# ac_proj.net
KiCad netlist of a schematic drawn in EAGLE
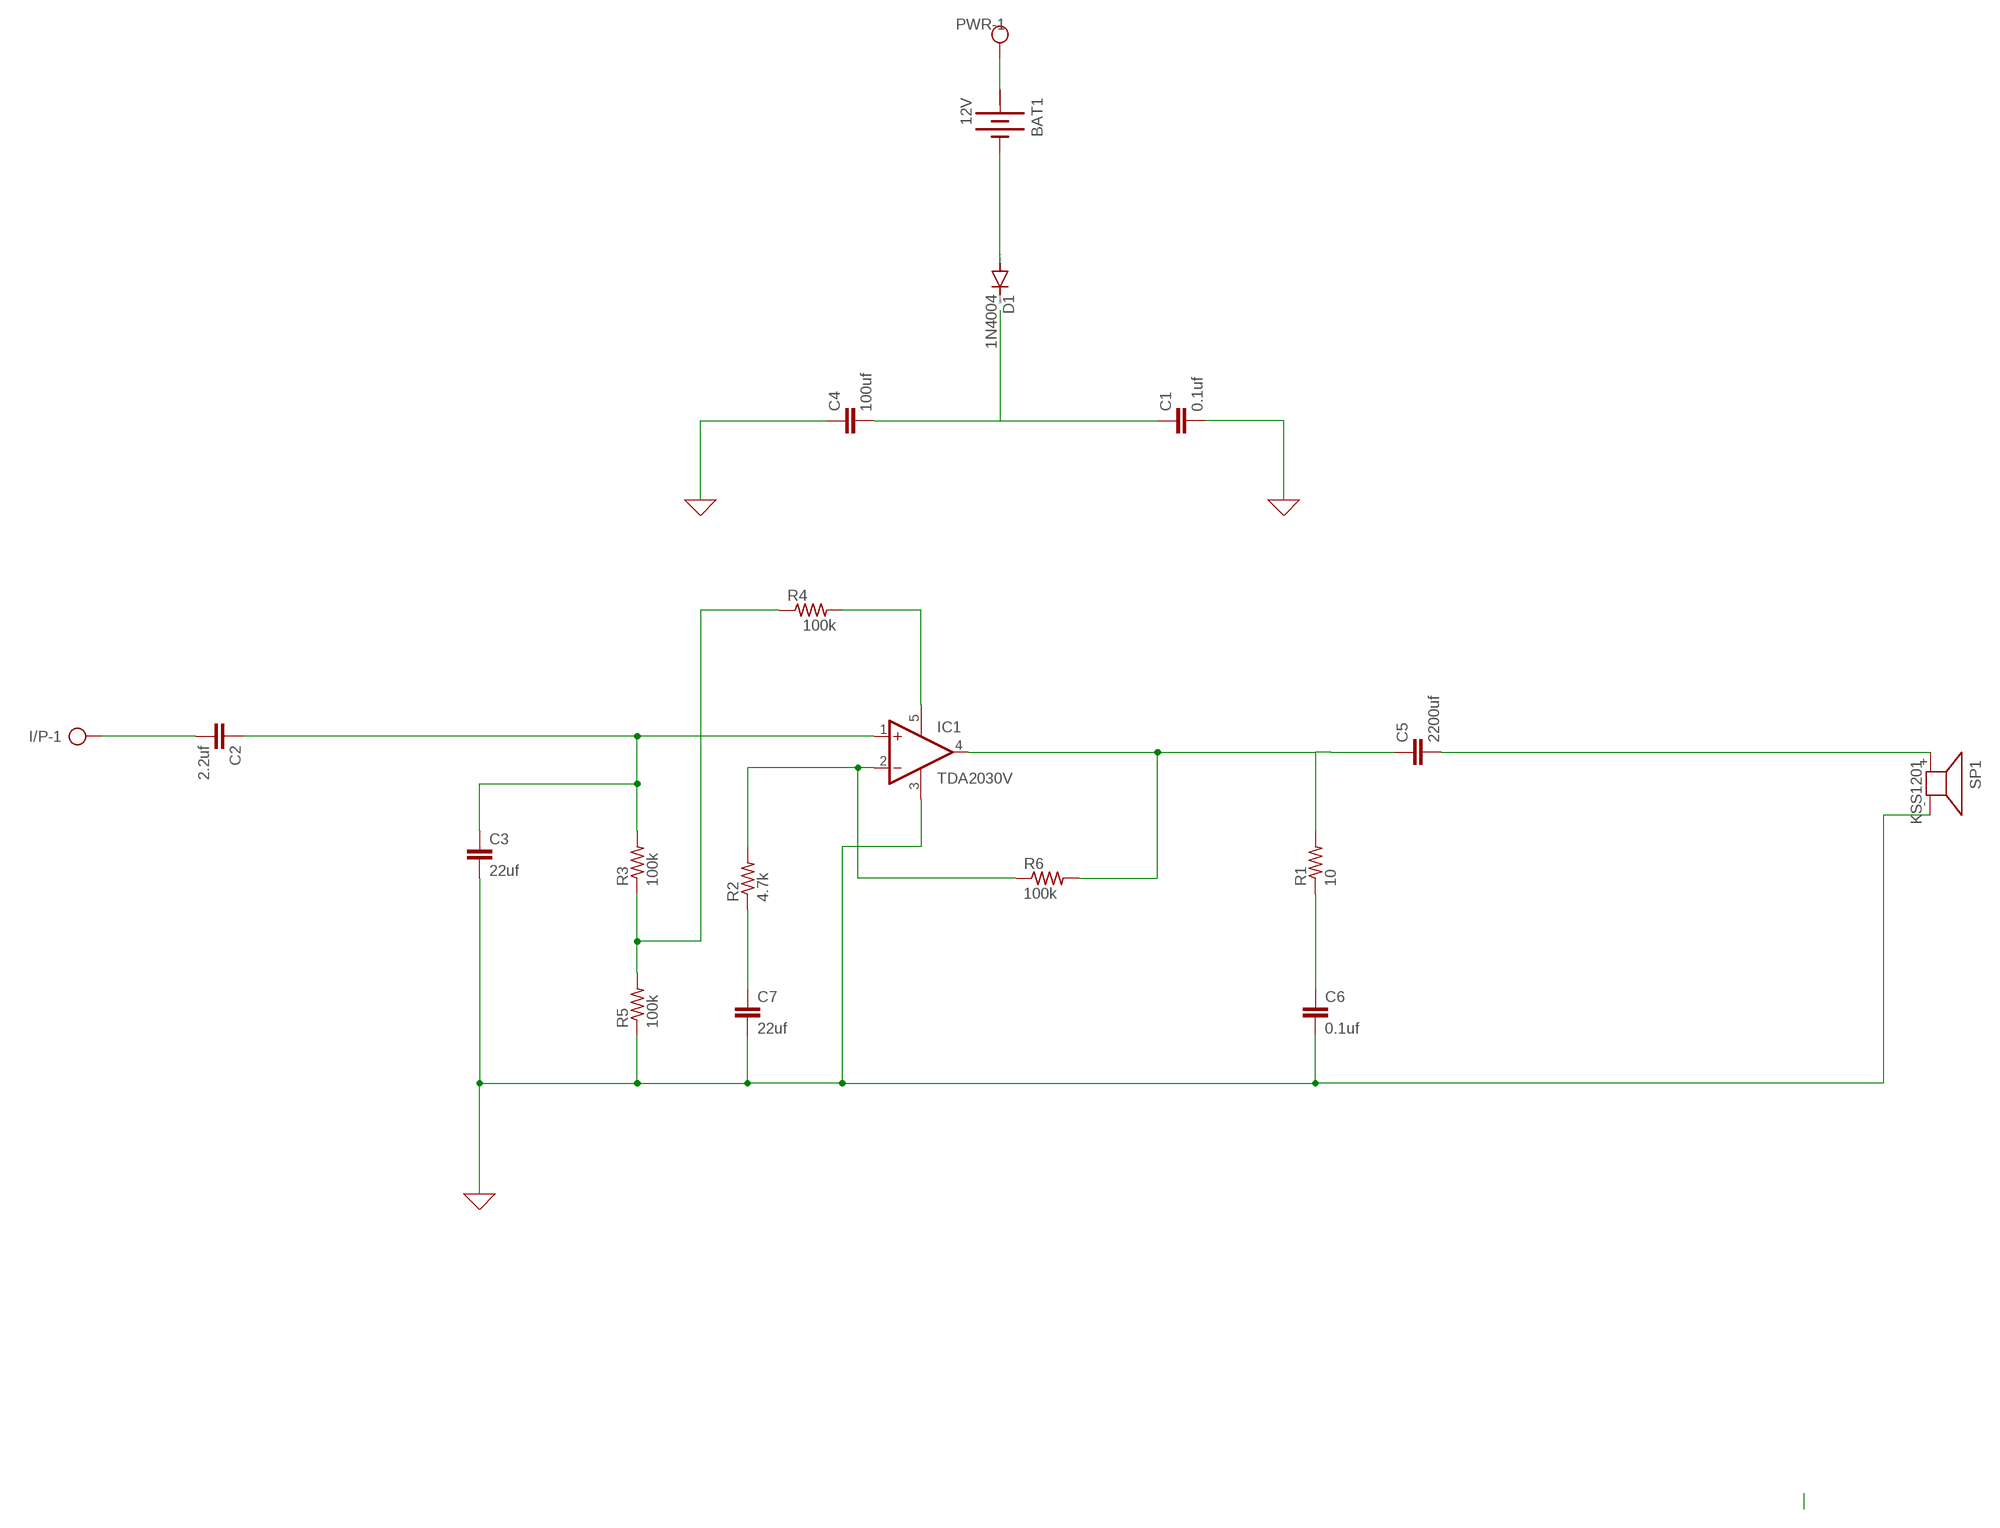
[diagram p0: schematic, sheet 1]

(export (version "E")
  (design (tool "Eeschema 10.0.6"))
  (components
    (comp (ref "BAT1")
      (value "12V")
      (footprint "eagle-import:BATTERY")
      (libsource (lib "eagle-import") (part "BATTERY"))
    )
    (comp (ref "C1")
      (value "0.1uf")
      (footprint "eagle-import:C5B3")
      (libsource (lib "eagle-import") (part "C5/3"))
    )
    (comp (ref "C2")
      (value "2.2uf")
      (footprint "eagle-import:C5B3")
      (libsource (lib "eagle-import") (part "C5/3"))
    )
    (comp (ref "C3")
      (value "22uf")
      (footprint "eagle-import:C5B3")
      (libsource (lib "eagle-import") (part "C5/3"))
    )
    (comp (ref "C4")
      (value "100uf")
      (footprint "eagle-import:C5B3")
      (libsource (lib "eagle-import") (part "C5/3"))
    )
    (comp (ref "C5")
      (value "2200uf")
      (footprint "eagle-import:C5B3")
      (libsource (lib "eagle-import") (part "C5/3"))
    )
    (comp (ref "C6")
      (value "0.1uf")
      (footprint "eagle-import:C5B3")
      (libsource (lib "eagle-import") (part "C5/3"))
    )
    (comp (ref "C7")
      (value "22uf")
      (footprint "eagle-import:C5B3")
      (libsource (lib "eagle-import") (part "C5/3"))
    )
    (comp (ref "D1")
      (value "1N4004")
      (footprint "eagle-import:DO41-10")
      (libsource (lib "eagle-import") (part "1N4004"))
    )
    (comp (ref "I/P")
      (value "AK500/2-H")
      (footprint "eagle-import:AK500_2-H")
      (libsource (lib "eagle-import") (part "AK500/2-H"))
    )
    (comp (ref "IC1")
      (value "TDA2030V")
      (footprint "eagle-import:CB360")
      (libsource (lib "eagle-import") (part "TDA2030V"))
    )
    (comp (ref "PWR")
      (value "AK500/2-H")
      (footprint "eagle-import:AK500_2-H")
      (libsource (lib "eagle-import") (part "AK500/2-H"))
    )
    (comp (ref "R1")
      (value "10")
      (footprint "eagle-import:0411_15")
      (libsource (lib "eagle-import") (part "R-US_0411/15"))
    )
    (comp (ref "R2")
      (value "4.7k")
      (footprint "eagle-import:0411_15")
      (libsource (lib "eagle-import") (part "R-US_0411/15"))
    )
    (comp (ref "R3")
      (value "100k")
      (footprint "eagle-import:0411_15")
      (libsource (lib "eagle-import") (part "R-US_0411/15"))
    )
    (comp (ref "R4")
      (value "100k")
      (footprint "eagle-import:0411_15")
      (libsource (lib "eagle-import") (part "R-US_0411/15"))
    )
    (comp (ref "R5")
      (value "100k")
      (footprint "eagle-import:0411_15")
      (libsource (lib "eagle-import") (part "R-US_0411/15"))
    )
    (comp (ref "R6")
      (value "100k")
      (footprint "eagle-import:0411_15")
      (libsource (lib "eagle-import") (part "R-US_0411/15"))
    )
    (comp (ref "SP1")
      (value "KSS1201")
      (footprint "eagle-import:KSS1201")
      (libsource (lib "eagle-import") (part "KSS1201"))
    )
  )
  (nets
    (net (code "1") (name "/+") (class "Default")
      (node (ref "BAT1") (pin "+@1") (pinfunction "+_+@1") (pintype "power_in"))
    )
    (net (code "2") (name "GND") (class "Default")
      (node (ref "C1") (pin "2") (pinfunction "2_2") (pintype "passive"))
      (node (ref "C3") (pin "2") (pinfunction "2_2") (pintype "passive"))
      (node (ref "C4") (pin "1") (pinfunction "1_1") (pintype "passive"))
      (node (ref "C6") (pin "2") (pinfunction "2_2") (pintype "passive"))
      (node (ref "C7") (pin "2") (pinfunction "2_2") (pintype "passive"))
      (node (ref "IC1") (pin "3") (pinfunction "GND_3") (pintype "power_in"))
      (node (ref "R5") (pin "1") (pinfunction "1_1") (pintype "passive"))
      (node (ref "SP1") (pin "-") (pinfunction "2_-") (pintype "passive"))
    )
    (net (code "3") (name "Net-(BAT1-Pad-)") (class "Default")
      (node (ref "BAT1") (pin "-") (pinfunction "-_-") (pintype "power_in"))
      (node (ref "D1") (pin "A") (pinfunction "A_A") (pintype "passive"))
    )
    (net (code "4") (name "Net-(C1-Pad1)") (class "Default")
      (node (ref "C1") (pin "1") (pinfunction "1_1") (pintype "passive"))
      (node (ref "C4") (pin "2") (pinfunction "2_2") (pintype "passive"))
    )
    (net (code "5") (name "Net-(C6-Pad1)") (class "Default")
      (node (ref "C6") (pin "1") (pinfunction "1_1") (pintype "passive"))
      (node (ref "R1") (pin "1") (pinfunction "1_1") (pintype "passive"))
    )
    (net (code "6") (name "Net-(C7-Pad1)") (class "Default")
      (node (ref "C7") (pin "1") (pinfunction "1_1") (pintype "passive"))
      (node (ref "R2") (pin "1") (pinfunction "1_1") (pintype "passive"))
    )
    (net (code "7") (name "Net-(I/PA-KL)") (class "Default")
      (node (ref "C2") (pin "2") (pinfunction "2_2") (pintype "passive"))
      (node (ref "I/P") (pin "1") (pinfunction "KL_1") (pintype "passive"))
    )
    (net (code "8") (name "Net-(IC1-+IN)") (class "Default")
      (node (ref "C2") (pin "1") (pinfunction "1_1") (pintype "passive"))
      (node (ref "C3") (pin "1") (pinfunction "1_1") (pintype "passive"))
      (node (ref "IC1") (pin "1") (pinfunction "+IN_1") (pintype "input"))
      (node (ref "R3") (pin "2") (pinfunction "2_2") (pintype "passive"))
    )
    (net (code "9") (name "Net-(IC1--IN)") (class "Default")
      (node (ref "IC1") (pin "2") (pinfunction "-IN_2") (pintype "input"))
      (node (ref "R2") (pin "2") (pinfunction "2_2") (pintype "passive"))
      (node (ref "R6") (pin "1") (pinfunction "1_1") (pintype "passive"))
    )
    (net (code "10") (name "Net-(IC1-OUT)") (class "Default")
      (node (ref "C5") (pin "1") (pinfunction "1_1") (pintype "passive"))
      (node (ref "IC1") (pin "4") (pinfunction "OUT_4") (pintype "output"))
      (node (ref "R1") (pin "2") (pinfunction "2_2") (pintype "passive"))
      (node (ref "R6") (pin "2") (pinfunction "2_2") (pintype "passive"))
    )
    (net (code "11") (name "Net-(IC1-V+)") (class "Default")
      (node (ref "IC1") (pin "5") (pinfunction "V+_5") (pintype "power_in"))
      (node (ref "R4") (pin "2") (pinfunction "2_2") (pintype "passive"))
    )
    (net (code "12") (name "Net-(PWRA-KL)") (class "Default")
      (node (ref "BAT1") (pin "+") (pinfunction "+_+") (pintype "power_in"))
      (node (ref "PWR") (pin "1") (pinfunction "KL_1") (pintype "passive"))
    )
    (net (code "13") (name "Net-(R3-Pad1)") (class "Default")
      (node (ref "R3") (pin "1") (pinfunction "1_1") (pintype "passive"))
      (node (ref "R4") (pin "1") (pinfunction "1_1") (pintype "passive"))
      (node (ref "R5") (pin "2") (pinfunction "2_2") (pintype "passive"))
    )
    (net (code "14") (name "Net-(SP1-1)") (class "Default")
      (node (ref "C5") (pin "2") (pinfunction "2_2") (pintype "passive"))
      (node (ref "SP1") (pin "+") (pinfunction "1_+") (pintype "passive"))
    )
    (net (code "15") (name "unconnected-(D1-PadC)") (class "Default")
      (node (ref "D1") (pin "C") (pinfunction "C_C") (pintype "passive"))
    )
  )
)
